# Sheet1.net
KiCad netlist of a schematic drawn in Altium Designer
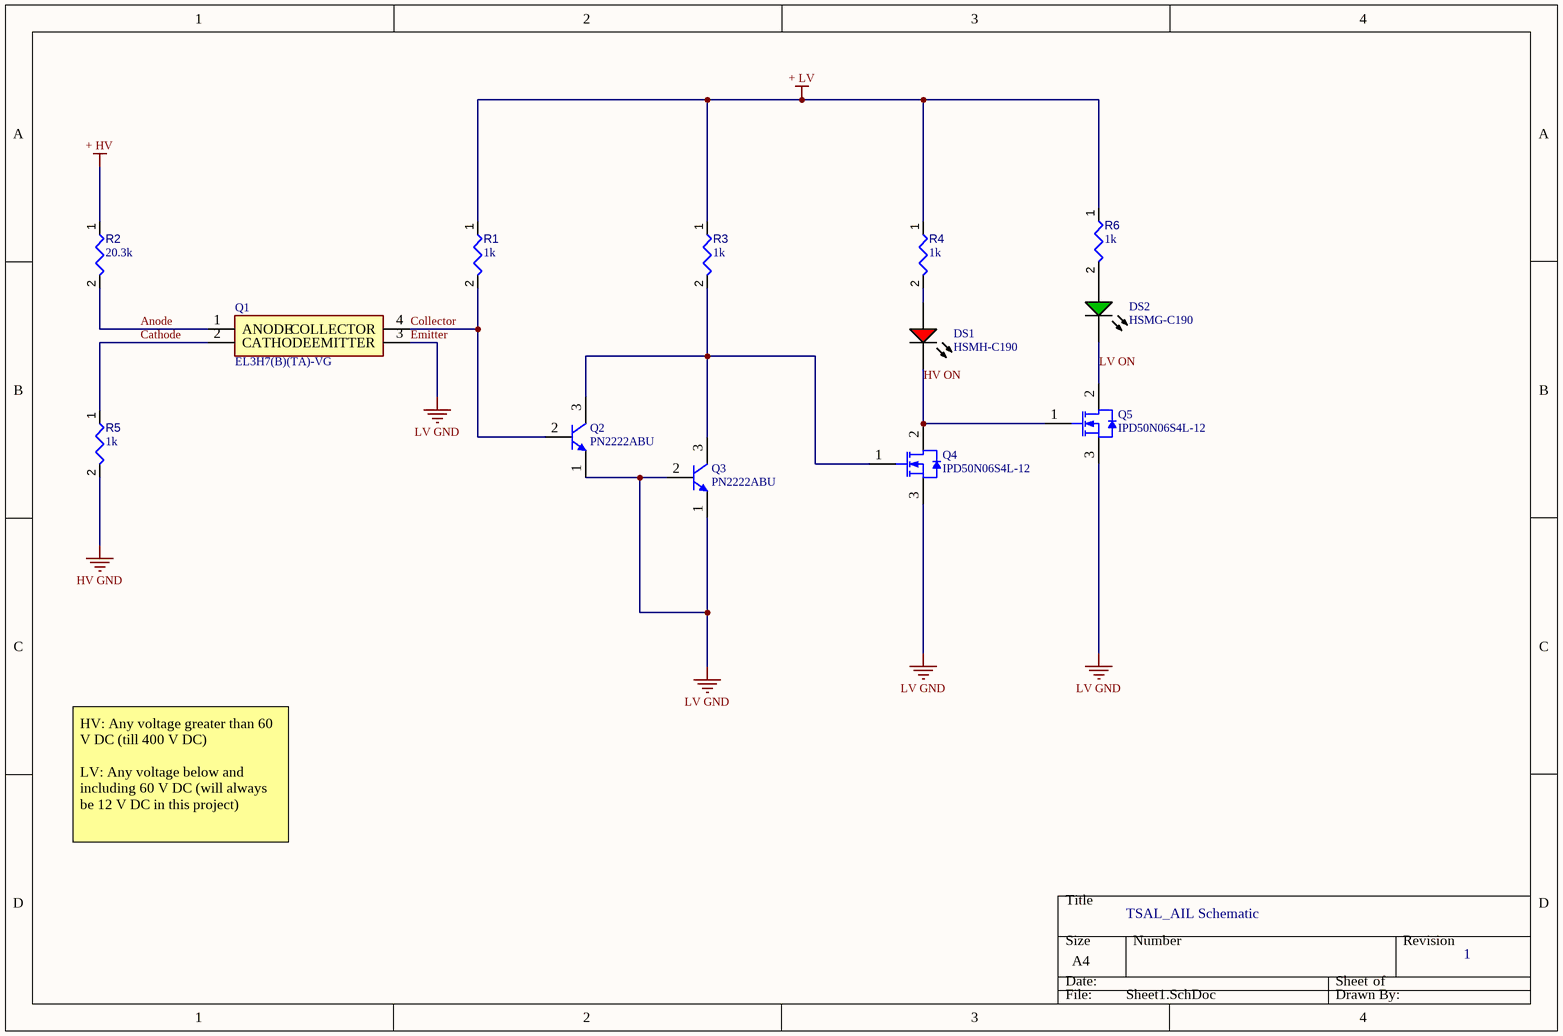
[diagram p0: Sheet1.SchDoc]

(export (version "E")
  (design (tool "Eeschema 10.0.6"))
  (components
    (comp (ref "DS1")
      (value "HSMH-C190")
      (footprint "AVAG-HSMX-C190_V")
      (description "LED Uni-Color Red, 65 mW, 20 mA, -40 to 85 degC, 2-Pin SMD, RoHS, Tape and Reel")
      (fields (field (name "POWER") "78mW") (field (name "MANUFACTURER") "Avago"))
      (libsource (lib "SFU Team Phantom") (part "LED-RED-AK-2"))
    )
    (comp (ref "DS2")
      (value "HSMG-C190")
      (footprint "AVAG-HSMX-C190_V")
      (description "LED Uni-Color Green, 52 mW, 20 mA, -40 to 85 degC, 2-Pin SMD, RoHS, Tape and Reel")
      (fields (field (name "POWER") "52mW") (field (name "MANUFACTURER") "Avago"))
      (libsource (lib "SFU Team Phantom") (part "LED-GREEN-AK-2"))
    )
    (comp (ref "Q1")
      (value "EL3H7(B)(TA)-VG")
      (footprint "SamacSys:SOIC127P700X200-4N")
      (description "Phototransistor")
      (fields (field (name "MOUSER PART NUMBER") "638-EL3H7BTAVG"))
      (libsource (lib "*") (part "EL3H7_B__TA_-VG"))
    )
    (comp (ref "Q2")
      (value "PN2222ABU")
      (footprint "FAIR-TO-92")
      (description "NPN General-Purpose Amplifier, 40 V, -55 to 150 degC, 3-Pin TO-92, RoHS, Bulk")
      (fields (field (name "POWER") "625mW") (field (name "MANUFACTURER") "Fairchild"))
      (libsource (lib "SFU Team Phantom") (part "BJT-NPN-EBC-3"))
    )
    (comp (ref "Q3")
      (value "PN2222ABU")
      (footprint "FAIR-TO-92")
      (description "NPN General-Purpose Amplifier, 40 V, -55 to 150 degC, 3-Pin TO-92, RoHS, Bulk")
      (fields (field (name "POWER") "625mW") (field (name "MANUFACTURER") "Fairchild"))
      (libsource (lib "SFU Team Phantom") (part "BJT-NPN-EBC-3"))
    )
    (comp (ref "Q4")
      (value "IPD50N06S4L-12")
      (footprint "INF-PG-TO252-3-11_M")
      (description "OptiMOS-T2 Power-Transistor, 60 V VDS, 50 A ID, PG-TO252-3-11, Reel, Green")
      (fields (field (name "MANUFACTURER") "Infineon"))
      (libsource (lib "Altium Content Vault") (part "INF-MOSFET-N-3"))
    )
    (comp (ref "Q5")
      (value "IPD50N06S4L-12")
      (footprint "INF-PG-TO252-3-11_M")
      (description "OptiMOS-T2 Power-Transistor, 60 V VDS, 50 A ID, PG-TO252-3-11, Reel, Green")
      (fields (field (name "MANUFACTURER") "Infineon"))
      (libsource (lib "Altium Content Vault") (part "INF-MOSFET-N-3"))
    )
    (comp (ref "R1")
      (value "1k")
      (footprint "RESC0402(1005)_L")
      (description "Chip Resistor, 84,5 kOhms, +/-1 %, 63 mW, -55 to 155 degC, 0402")
      (fields (field (name "TOLERANCE") "1%") (field (name "POWER") "63mW"))
      (libsource (lib "SFU Team Phantom") (part "RES-2"))
    )
    (comp (ref "R2")
      (value "20.3k")
      (footprint "RESC0402(1005)_L")
      (description "Chip Resistor, 84,5 kOhms, +/-1 %, 63 mW, -55 to 155 degC, 0402")
      (fields (field (name "TOLERANCE") "1%") (field (name "POWER") "63mW"))
      (libsource (lib "SFU Team Phantom") (part "RES-2"))
    )
    (comp (ref "R3")
      (value "1k")
      (footprint "RESC0402(1005)_L")
      (description "Chip Resistor, 84,5 kOhms, +/-1 %, 63 mW, -55 to 155 degC, 0402")
      (fields (field (name "TOLERANCE") "1%") (field (name "POWER") "63mW"))
      (libsource (lib "SFU Team Phantom") (part "RES-2"))
    )
    (comp (ref "R4")
      (value "1k")
      (footprint "RESC0402(1005)_L")
      (description "Chip Resistor, 84,5 kOhms, +/-1 %, 63 mW, -55 to 155 degC, 0402")
      (fields (field (name "TOLERANCE") "1%") (field (name "POWER") "63mW"))
      (libsource (lib "SFU Team Phantom") (part "RES-2"))
    )
    (comp (ref "R5")
      (value "1k")
      (footprint "RESC0402(1005)_L")
      (description "Chip Resistor, 84,5 kOhms, +/-1 %, 63 mW, -55 to 155 degC, 0402")
      (fields (field (name "TOLERANCE") "1%") (field (name "POWER") "63mW"))
      (libsource (lib "SFU Team Phantom") (part "RES-2"))
    )
    (comp (ref "R6")
      (value "1k")
      (footprint "RESC0402(1005)_L")
      (description "Chip Resistor, 84,5 kOhms, +/-1 %, 63 mW, -55 to 155 degC, 0402")
      (fields (field (name "TOLERANCE") "1%") (field (name "POWER") "63mW"))
      (libsource (lib "SFU Team Phantom") (part "RES-2"))
    )
  )
  (nets
    (net (code "1") (name "+ HV") (class "Default")
      (node (ref "R2") (pin "1") (pinfunction "1_1") (pintype "passive"))
    )
    (net (code "2") (name "+ LV") (class "Default")
      (node (ref "R1") (pin "1") (pinfunction "1_1") (pintype "passive"))
      (node (ref "R3") (pin "1") (pinfunction "1_1") (pintype "passive"))
      (node (ref "R4") (pin "1") (pinfunction "1_1") (pintype "passive"))
      (node (ref "R6") (pin "1") (pinfunction "1_1") (pintype "passive"))
    )
    (net (code "3") (name "/Anode") (class "Default")
      (node (ref "Q1") (pin "1") (pinfunction "ANODE_1") (pintype "passive"))
      (node (ref "R2") (pin "2") (pinfunction "2_2") (pintype "passive"))
    )
    (net (code "4") (name "/Cathode") (class "Default")
      (node (ref "Q1") (pin "2") (pinfunction "CATHODE_2") (pintype "passive"))
      (node (ref "R5") (pin "1") (pinfunction "1_1") (pintype "passive"))
    )
    (net (code "5") (name "/Collector") (class "Default")
      (node (ref "Q1") (pin "4") (pinfunction "COLLECTOR_4") (pintype "passive"))
      (node (ref "Q2") (pin "2") (pinfunction "B_2") (pintype "passive"))
      (node (ref "R1") (pin "2") (pinfunction "2_2") (pintype "passive"))
    )
    (net (code "6") (name "/HV ON") (class "Default")
      (node (ref "DS1") (pin "2") (pinfunction "K_2") (pintype "passive"))
      (node (ref "Q4") (pin "2") (pinfunction "DRAIN_2") (pintype "passive"))
      (node (ref "Q5") (pin "1") (pinfunction "GATE_1") (pintype "passive"))
    )
    (net (code "7") (name "/LV ON") (class "Default")
      (node (ref "DS2") (pin "2") (pinfunction "K_2") (pintype "passive"))
      (node (ref "Q5") (pin "2") (pinfunction "DRAIN_2") (pintype "passive"))
    )
    (net (code "8") (name "HV GND") (class "Default")
      (node (ref "R5") (pin "2") (pinfunction "2_2") (pintype "passive"))
    )
    (net (code "9") (name "LV GND") (class "Default")
      (node (ref "Q1") (pin "3") (pinfunction "EMITTER_3") (pintype "passive"))
      (node (ref "Q2") (pin "1") (pinfunction "E_1") (pintype "passive"))
      (node (ref "Q3") (pin "1") (pinfunction "E_1") (pintype "passive"))
      (node (ref "Q3") (pin "2") (pinfunction "B_2") (pintype "passive"))
      (node (ref "Q4") (pin "3") (pinfunction "SOURCE_3") (pintype "passive"))
      (node (ref "Q5") (pin "3") (pinfunction "SOURCE_3") (pintype "passive"))
    )
    (net (code "10") (name "Net-(DS1-A)") (class "Default")
      (node (ref "DS1") (pin "1") (pinfunction "A_1") (pintype "passive"))
      (node (ref "R4") (pin "2") (pinfunction "2_2") (pintype "passive"))
    )
    (net (code "11") (name "Net-(DS2-A)") (class "Default")
      (node (ref "DS2") (pin "1") (pinfunction "A_1") (pintype "passive"))
      (node (ref "R6") (pin "2") (pinfunction "2_2") (pintype "passive"))
    )
    (net (code "12") (name "Net-(Q2-C)") (class "Default")
      (node (ref "Q2") (pin "3") (pinfunction "C_3") (pintype "passive"))
      (node (ref "Q3") (pin "3") (pinfunction "C_3") (pintype "passive"))
      (node (ref "Q4") (pin "1") (pinfunction "GATE_1") (pintype "passive"))
      (node (ref "R3") (pin "2") (pinfunction "2_2") (pintype "passive"))
    )
  )
)
